# PDB_SR.net
KiCad netlist of a schematic drawn in EAGLE
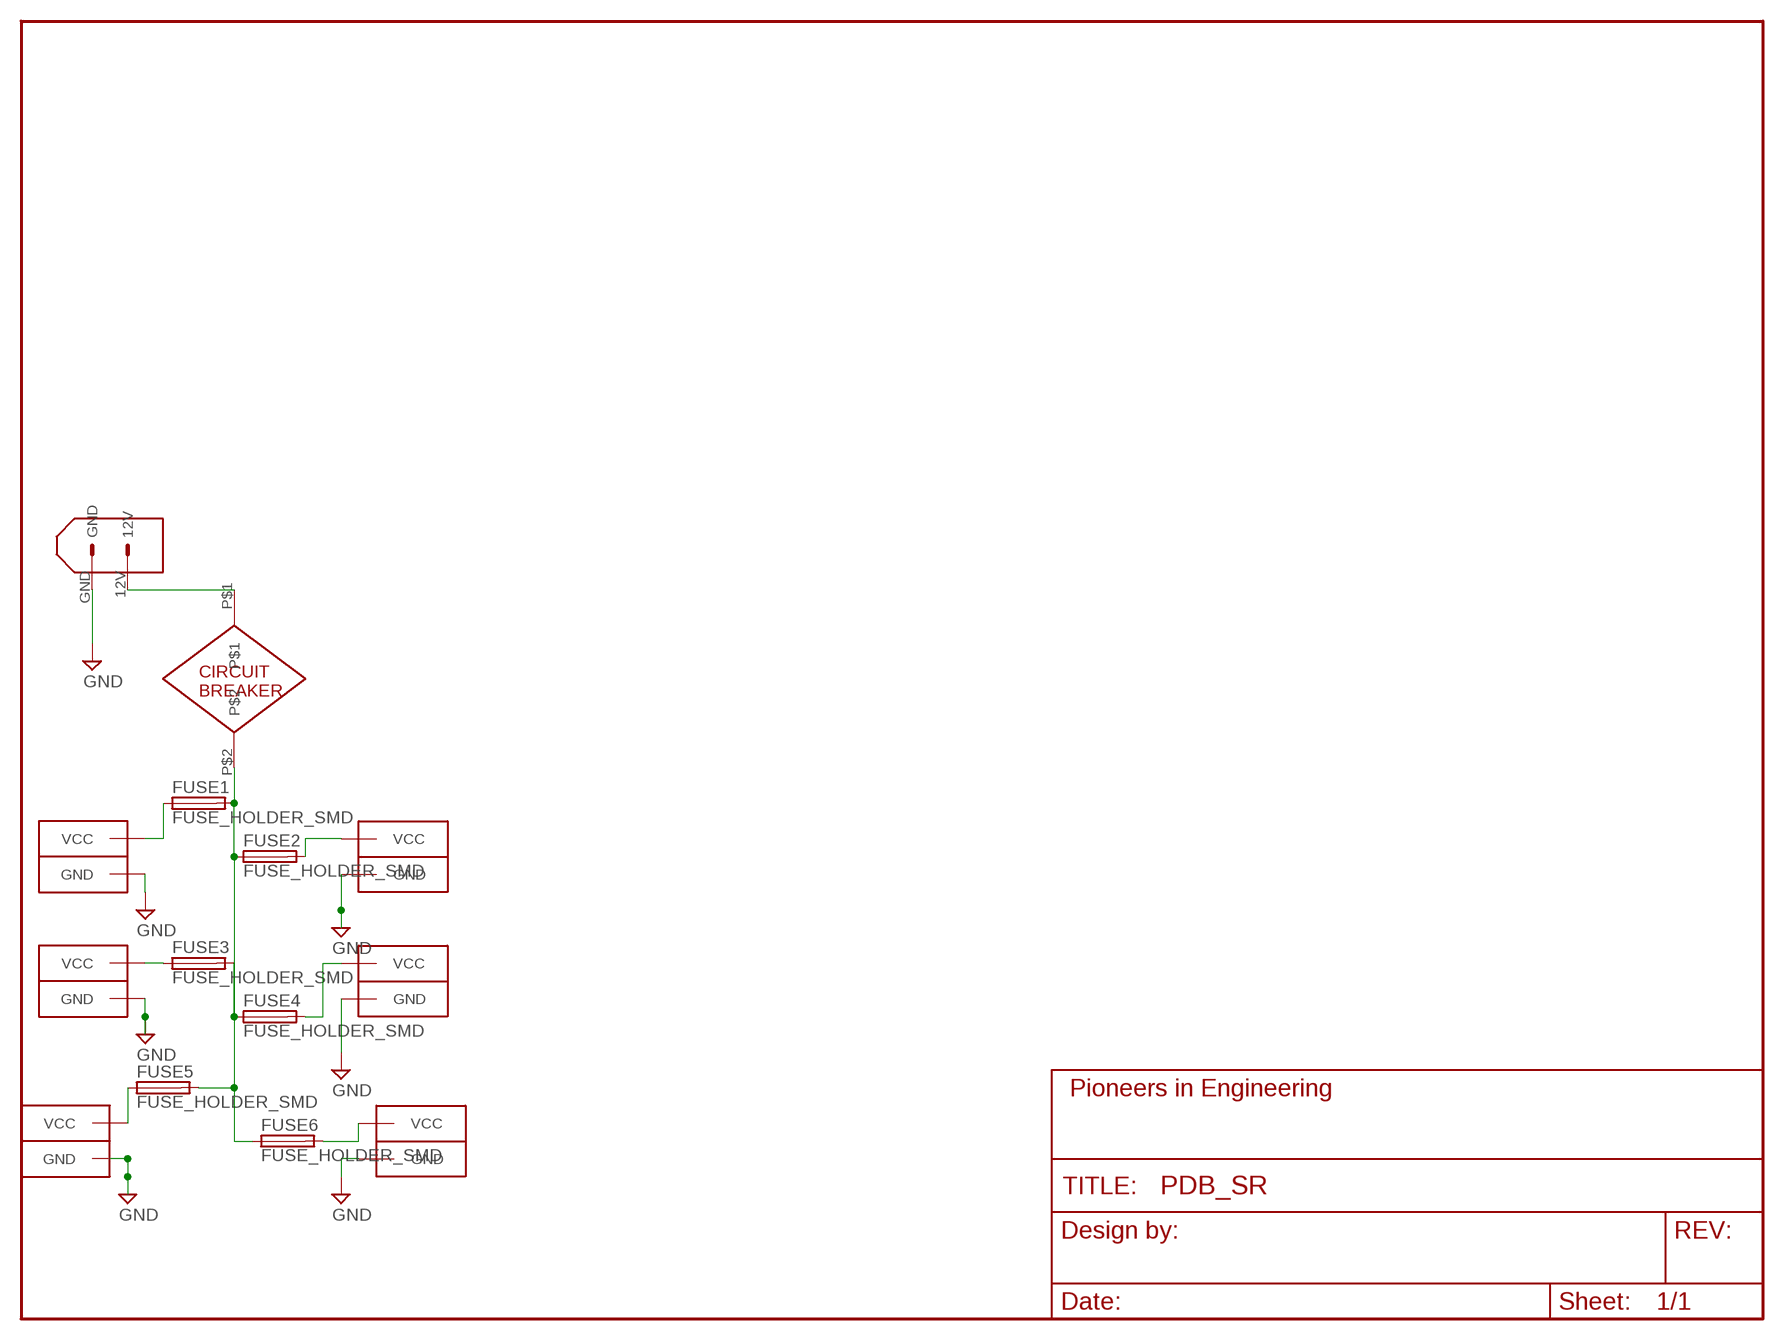
[diagram p0: schematic, sheet 1]

(export (version "E")
  (design (tool "Eeschema 10.0.6"))
  (components
    (comp (ref "CIRCUIT_BREAKER")
      (value "CIRC_BREAKER")
      (footprint "eagle-import:CIRC_BREAKER")
      (libsource (lib "eagle-import") (part "CIRC_BREAKER"))
    )
    (comp (ref "CONN1")
      (value "ANDERSONHORIZONTAL")
      (footprint "eagle-import:ANDERSON_HORIZONTAL")
      (libsource (lib "eagle-import") (part "ANDERSONHORIZONTAL"))
    )
    (comp (ref "CONN2")
      (value "ANDERSONHORIZONTAL")
      (footprint "eagle-import:ANDERSON_HORIZONTAL")
      (libsource (lib "eagle-import") (part "ANDERSONHORIZONTAL"))
    )
    (comp (ref "CONN3")
      (value "ANDERSONHORIZONTAL")
      (footprint "eagle-import:ANDERSON_HORIZONTAL")
      (libsource (lib "eagle-import") (part "ANDERSONHORIZONTAL"))
    )
    (comp (ref "CONN4")
      (value "ANDERSONHORIZONTAL")
      (footprint "eagle-import:ANDERSON_HORIZONTAL")
      (libsource (lib "eagle-import") (part "ANDERSONHORIZONTAL"))
    )
    (comp (ref "CONN5")
      (value "ANDERSONHORIZONTAL")
      (footprint "eagle-import:ANDERSON_HORIZONTAL")
      (libsource (lib "eagle-import") (part "ANDERSONHORIZONTAL"))
    )
    (comp (ref "CONN6")
      (value "ANDERSONHORIZONTAL")
      (footprint "eagle-import:ANDERSON_HORIZONTAL")
      (libsource (lib "eagle-import") (part "ANDERSONHORIZONTAL"))
    )
    (comp (ref "FUSE1")
      (value "FUSE_HOLDER_SMD")
      (footprint "eagle-import:FUSE_HOLDER_SMD")
      (libsource (lib "eagle-import") (part "FUSE_HOLDER_SMD"))
    )
    (comp (ref "FUSE2")
      (value "FUSE_HOLDER_SMD")
      (footprint "eagle-import:FUSE_HOLDER_SMD")
      (libsource (lib "eagle-import") (part "FUSE_HOLDER_SMD"))
    )
    (comp (ref "FUSE3")
      (value "FUSE_HOLDER_SMD")
      (footprint "eagle-import:FUSE_HOLDER_SMD")
      (libsource (lib "eagle-import") (part "FUSE_HOLDER_SMD"))
    )
    (comp (ref "FUSE4")
      (value "FUSE_HOLDER_SMD")
      (footprint "eagle-import:FUSE_HOLDER_SMD")
      (libsource (lib "eagle-import") (part "FUSE_HOLDER_SMD"))
    )
    (comp (ref "FUSE5")
      (value "FUSE_HOLDER_SMD")
      (footprint "eagle-import:FUSE_HOLDER_SMD")
      (libsource (lib "eagle-import") (part "FUSE_HOLDER_SMD"))
    )
    (comp (ref "FUSE6")
      (value "FUSE_HOLDER_SMD")
      (footprint "eagle-import:FUSE_HOLDER_SMD")
      (libsource (lib "eagle-import") (part "FUSE_HOLDER_SMD"))
    )
    (comp (ref "U$1")
      (value "XT60CONNECTOR")
      (footprint "eagle-import:XT60CONNECTOR")
      (fields (field (name "PARTNUMBER") "PRT-10474 "))
      (libsource (lib "eagle-import") (part "XT60CONNECTOR"))
    )
  )
  (nets
    (net (code "1") (name "GND") (class "Default")
      (node (ref "CONN1") (pin "PIN1") (pinfunction "GND_PIN1") (pintype "bidirectional"))
      (node (ref "CONN1") (pin "PIN1-LEAD") (pinfunction "GND_PIN1-LEAD") (pintype "bidirectional"))
      (node (ref "CONN2") (pin "PIN1") (pinfunction "GND_PIN1") (pintype "bidirectional"))
      (node (ref "CONN2") (pin "PIN1-LEAD") (pinfunction "GND_PIN1-LEAD") (pintype "bidirectional"))
      (node (ref "CONN3") (pin "PIN1") (pinfunction "GND_PIN1") (pintype "bidirectional"))
      (node (ref "CONN3") (pin "PIN1-LEAD") (pinfunction "GND_PIN1-LEAD") (pintype "bidirectional"))
      (node (ref "CONN4") (pin "PIN1") (pinfunction "GND_PIN1") (pintype "bidirectional"))
      (node (ref "CONN4") (pin "PIN1-LEAD") (pinfunction "GND_PIN1-LEAD") (pintype "bidirectional"))
      (node (ref "CONN5") (pin "PIN1") (pinfunction "GND_PIN1") (pintype "bidirectional"))
      (node (ref "CONN5") (pin "PIN1-LEAD") (pinfunction "GND_PIN1-LEAD") (pintype "bidirectional"))
      (node (ref "CONN6") (pin "PIN1") (pinfunction "GND_PIN1") (pintype "bidirectional"))
      (node (ref "CONN6") (pin "PIN1-LEAD") (pinfunction "GND_PIN1-LEAD") (pintype "bidirectional"))
      (node (ref "U$1") (pin "GND") (pinfunction "GND_GND") (pintype "bidirectional"))
    )
    (net (code "2") (name "Net-(CIRCUIT_BREAKER-PadP$1)") (class "Default")
      (node (ref "CIRCUIT_BREAKER") (pin "P$1") (pinfunction "P$1_P$1") (pintype "bidirectional"))
      (node (ref "U$1") (pin "12V") (pinfunction "12V_12V") (pintype "bidirectional"))
    )
    (net (code "3") (name "Net-(CIRCUIT_BREAKER-PadP$2)") (class "Default")
      (node (ref "CIRCUIT_BREAKER") (pin "P$2") (pinfunction "P$2_P$2") (pintype "bidirectional"))
      (node (ref "FUSE1") (pin "P$2_DOWN") (pinfunction "2_P$2_DOWN") (pintype "passive"))
      (node (ref "FUSE1") (pin "P$2_UP") (pinfunction "2_P$2_UP") (pintype "passive"))
      (node (ref "FUSE2") (pin "P$1_DOWN") (pinfunction "1_P$1_DOWN") (pintype "passive"))
      (node (ref "FUSE2") (pin "P$1_UP") (pinfunction "1_P$1_UP") (pintype "passive"))
      (node (ref "FUSE3") (pin "P$2_DOWN") (pinfunction "2_P$2_DOWN") (pintype "passive"))
      (node (ref "FUSE3") (pin "P$2_UP") (pinfunction "2_P$2_UP") (pintype "passive"))
      (node (ref "FUSE4") (pin "P$1_DOWN") (pinfunction "1_P$1_DOWN") (pintype "passive"))
      (node (ref "FUSE4") (pin "P$1_UP") (pinfunction "1_P$1_UP") (pintype "passive"))
      (node (ref "FUSE5") (pin "P$2_DOWN") (pinfunction "2_P$2_DOWN") (pintype "passive"))
      (node (ref "FUSE5") (pin "P$2_UP") (pinfunction "2_P$2_UP") (pintype "passive"))
      (node (ref "FUSE6") (pin "P$1_DOWN") (pinfunction "1_P$1_DOWN") (pintype "passive"))
      (node (ref "FUSE6") (pin "P$1_UP") (pinfunction "1_P$1_UP") (pintype "passive"))
    )
    (net (code "4") (name "Net-(CONN1-VCC-PadPIN2)") (class "Default")
      (node (ref "CONN1") (pin "PIN2") (pinfunction "VCC_PIN2") (pintype "bidirectional"))
      (node (ref "CONN1") (pin "PIN2-LEAD") (pinfunction "VCC_PIN2-LEAD") (pintype "bidirectional"))
      (node (ref "FUSE3") (pin "P$1_DOWN") (pinfunction "1_P$1_DOWN") (pintype "passive"))
      (node (ref "FUSE3") (pin "P$1_UP") (pinfunction "1_P$1_UP") (pintype "passive"))
    )
    (net (code "5") (name "Net-(CONN2-VCC-PadPIN2)") (class "Default")
      (node (ref "CONN2") (pin "PIN2") (pinfunction "VCC_PIN2") (pintype "bidirectional"))
      (node (ref "CONN2") (pin "PIN2-LEAD") (pinfunction "VCC_PIN2-LEAD") (pintype "bidirectional"))
      (node (ref "FUSE1") (pin "P$1_DOWN") (pinfunction "1_P$1_DOWN") (pintype "passive"))
      (node (ref "FUSE1") (pin "P$1_UP") (pinfunction "1_P$1_UP") (pintype "passive"))
    )
    (net (code "6") (name "Net-(CONN3-VCC-PadPIN2)") (class "Default")
      (node (ref "CONN3") (pin "PIN2") (pinfunction "VCC_PIN2") (pintype "bidirectional"))
      (node (ref "CONN3") (pin "PIN2-LEAD") (pinfunction "VCC_PIN2-LEAD") (pintype "bidirectional"))
      (node (ref "FUSE5") (pin "P$1_DOWN") (pinfunction "1_P$1_DOWN") (pintype "passive"))
      (node (ref "FUSE5") (pin "P$1_UP") (pinfunction "1_P$1_UP") (pintype "passive"))
    )
    (net (code "7") (name "Net-(CONN4-VCC-PadPIN2)") (class "Default")
      (node (ref "CONN4") (pin "PIN2") (pinfunction "VCC_PIN2") (pintype "bidirectional"))
      (node (ref "CONN4") (pin "PIN2-LEAD") (pinfunction "VCC_PIN2-LEAD") (pintype "bidirectional"))
      (node (ref "FUSE2") (pin "P$2_DOWN") (pinfunction "2_P$2_DOWN") (pintype "passive"))
      (node (ref "FUSE2") (pin "P$2_UP") (pinfunction "2_P$2_UP") (pintype "passive"))
    )
    (net (code "8") (name "Net-(CONN5-VCC-PadPIN2)") (class "Default")
      (node (ref "CONN5") (pin "PIN2") (pinfunction "VCC_PIN2") (pintype "bidirectional"))
      (node (ref "CONN5") (pin "PIN2-LEAD") (pinfunction "VCC_PIN2-LEAD") (pintype "bidirectional"))
      (node (ref "FUSE4") (pin "P$2_DOWN") (pinfunction "2_P$2_DOWN") (pintype "passive"))
      (node (ref "FUSE4") (pin "P$2_UP") (pinfunction "2_P$2_UP") (pintype "passive"))
    )
    (net (code "9") (name "Net-(CONN6-VCC-PadPIN2)") (class "Default")
      (node (ref "CONN6") (pin "PIN2") (pinfunction "VCC_PIN2") (pintype "bidirectional"))
      (node (ref "CONN6") (pin "PIN2-LEAD") (pinfunction "VCC_PIN2-LEAD") (pintype "bidirectional"))
      (node (ref "FUSE6") (pin "P$2_DOWN") (pinfunction "2_P$2_DOWN") (pintype "passive"))
      (node (ref "FUSE6") (pin "P$2_UP") (pinfunction "2_P$2_UP") (pintype "passive"))
    )
  )
)
